# AudioThrowie.net
KiCad netlist of a schematic drawn in EAGLE
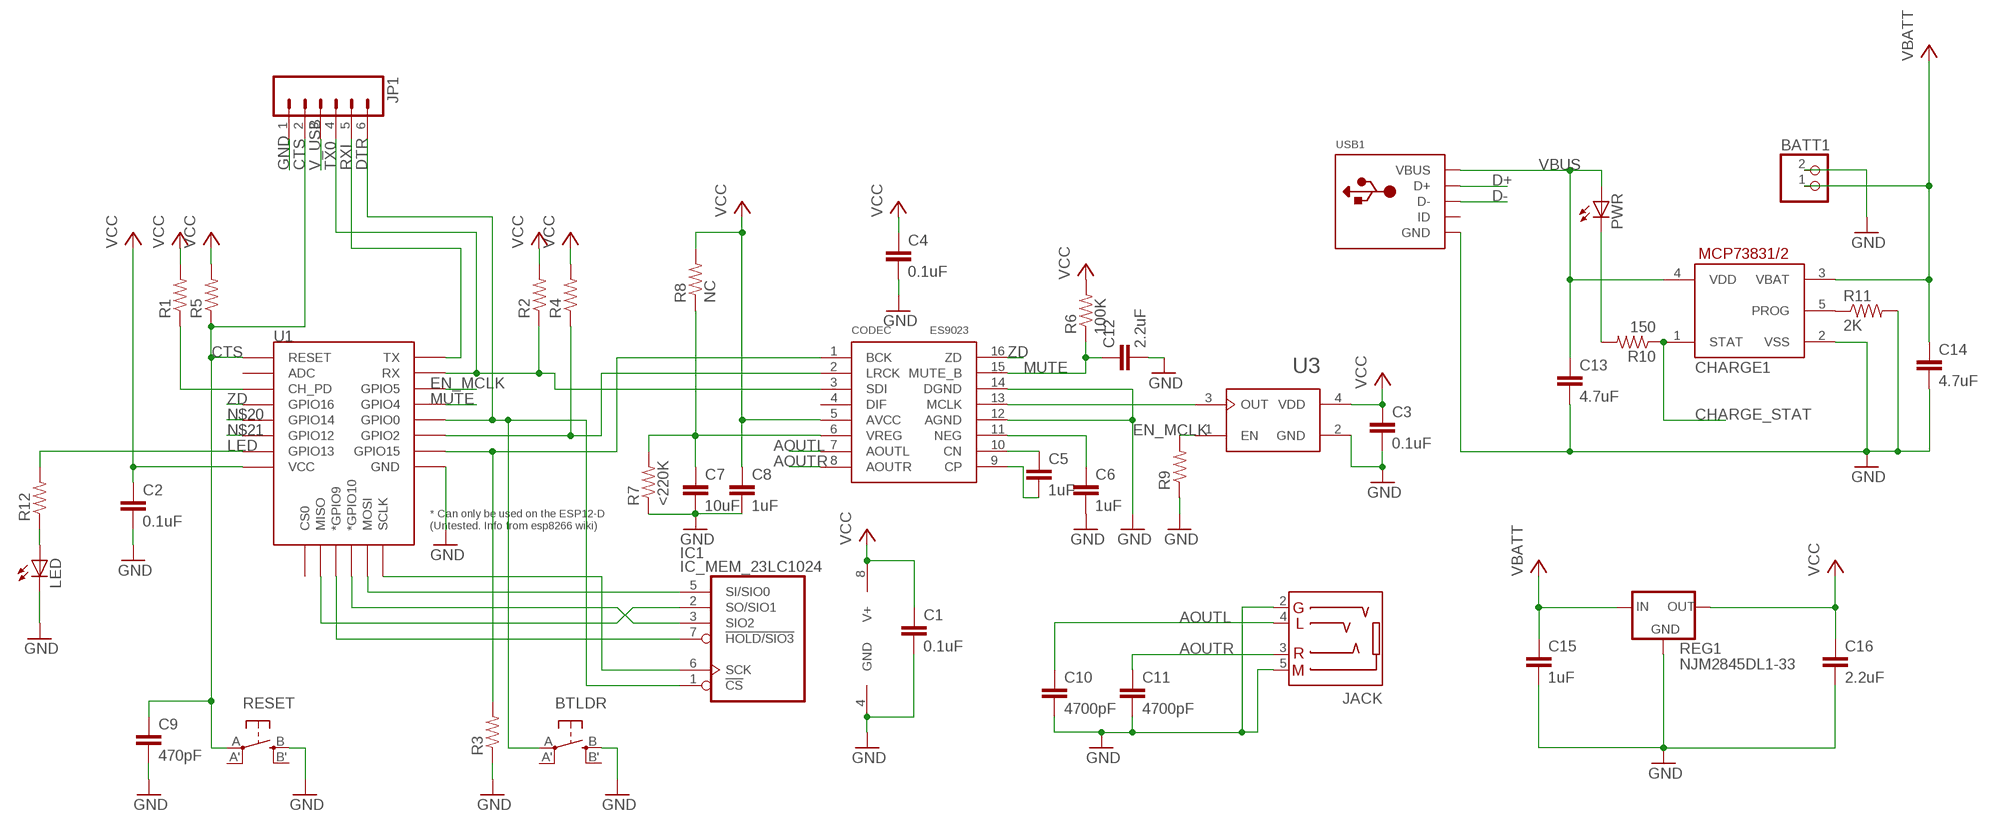
[diagram p0: schematic, sheet 1]

(export (version "E")
  (design (tool "Eeschema 10.0.6"))
  (components
    (comp (ref "BATT1")
      (value "JST_2PIN-THM")
      (footprint "eagle-import:JST-PH-2-THM")
      (libsource (lib "eagle-import") (part "JST_2PIN-THM"))
    )
    (comp (ref "BTLDR")
      (value "SPST_TACT-EVQQ2")
      (footprint "eagle-import:EVQ-Q2")
      (libsource (lib "eagle-import") (part "SPST_TACT-EVQQ2"))
    )
    (comp (ref "C1")
      (value "0.1uF")
      (footprint "eagle-import:0805")
      (libsource (lib "eagle-import") (part "CAP0805"))
    )
    (comp (ref "C2")
      (value "0.1uF")
      (footprint "eagle-import:0805")
      (libsource (lib "eagle-import") (part "CAP0805"))
    )
    (comp (ref "C3")
      (value "0.1uF")
      (footprint "eagle-import:0805")
      (libsource (lib "eagle-import") (part "CAP0805"))
    )
    (comp (ref "C4")
      (value "0.1uF")
      (footprint "eagle-import:0805")
      (libsource (lib "eagle-import") (part "CAP0805"))
    )
    (comp (ref "C5")
      (value "1uF")
      (footprint "eagle-import:0805")
      (libsource (lib "eagle-import") (part "CAP0805"))
    )
    (comp (ref "C6")
      (value "1uF")
      (footprint "eagle-import:0805")
      (libsource (lib "eagle-import") (part "CAP0805"))
    )
    (comp (ref "C7")
      (value "10uF")
      (footprint "eagle-import:0805")
      (libsource (lib "eagle-import") (part "CAP0805"))
    )
    (comp (ref "C8")
      (value "1uF")
      (footprint "eagle-import:0805")
      (libsource (lib "eagle-import") (part "CAP0805"))
    )
    (comp (ref "C9")
      (value "470pF")
      (footprint "eagle-import:0805")
      (libsource (lib "eagle-import") (part "CAP0805"))
    )
    (comp (ref "C10")
      (value "4700pF")
      (footprint "eagle-import:0805")
      (libsource (lib "eagle-import") (part "CAP0805"))
    )
    (comp (ref "C11")
      (value "4700pF")
      (footprint "eagle-import:0805")
      (libsource (lib "eagle-import") (part "CAP0805"))
    )
    (comp (ref "C12")
      (value "2.2uF")
      (footprint "eagle-import:0805")
      (libsource (lib "eagle-import") (part "CAP0805"))
    )
    (comp (ref "C13")
      (value "4.7uF")
      (footprint "eagle-import:0805")
      (libsource (lib "eagle-import") (part "CAP0805"))
    )
    (comp (ref "C14")
      (value "4.7uF")
      (footprint "eagle-import:0805")
      (libsource (lib "eagle-import") (part "CAP0805"))
    )
    (comp (ref "C15")
      (value "1uF")
      (footprint "eagle-import:0805")
      (libsource (lib "eagle-import") (part "CAP0805"))
    )
    (comp (ref "C16")
      (value "2.2uF")
      (footprint "eagle-import:0805")
      (libsource (lib "eagle-import") (part "CAP0805"))
    )
    (comp (ref "CHARGE1")
      (value "MCP73831/OT")
      (footprint "eagle-import:SOT23-5L")
      (libsource (lib "eagle-import") (part "MCP73831/OT"))
    )
    (comp (ref "CODEC")
      (value "ES9023")
      (footprint "eagle-import:SOP16")
      (libsource (lib "eagle-import") (part "ES9023"))
    )
    (comp (ref "IC1")
      (value "IC_MEM_23LC1024")
      (footprint "eagle-import:SOIC-8")
      (libsource (lib "eagle-import") (part "IC_MEM_23LC1024"))
    )
    (comp (ref "JACK")
      (value "AUDIO-STEREO-JACK-3.5MM-4SLEEVES")
      (footprint "eagle-import:PJ320D")
      (libsource (lib "eagle-import") (part "AUDIO-STEREO-JACK-3.5MM-4SLEEVES"))
    )
    (comp (ref "JP1")
      (value "M06LONGPADS")
      (footprint "eagle-import:1X06_LONGPADS")
      (libsource (lib "eagle-import") (part "M06LONGPADS"))
    )
    (comp (ref "LED")
      (value "LED3MM")
      (footprint "eagle-import:LED3MM")
      (libsource (lib "eagle-import") (part "LED3MM"))
    )
    (comp (ref "PWR")
      (value "LED3MM")
      (footprint "eagle-import:LED3MM")
      (libsource (lib "eagle-import") (part "LED3MM"))
    )
    (comp (ref "R1")
      (value "R-US_M0805")
      (footprint "eagle-import:M0805")
      (libsource (lib "eagle-import") (part "R-US_M0805"))
    )
    (comp (ref "R2")
      (value "R-US_M0805")
      (footprint "eagle-import:M0805")
      (libsource (lib "eagle-import") (part "R-US_M0805"))
    )
    (comp (ref "R3")
      (value "R-US_M0805")
      (footprint "eagle-import:M0805")
      (libsource (lib "eagle-import") (part "R-US_M0805"))
    )
    (comp (ref "R4")
      (value "R-US_M0805")
      (footprint "eagle-import:M0805")
      (libsource (lib "eagle-import") (part "R-US_M0805"))
    )
    (comp (ref "R5")
      (value "R-US_M0805")
      (footprint "eagle-import:M0805")
      (libsource (lib "eagle-import") (part "R-US_M0805"))
    )
    (comp (ref "R6")
      (value "100K")
      (footprint "eagle-import:M0805")
      (libsource (lib "eagle-import") (part "R-US_M0805"))
    )
    (comp (ref "R7")
      (value "<220K")
      (footprint "eagle-import:M0805")
      (libsource (lib "eagle-import") (part "R-US_M0805"))
    )
    (comp (ref "R8")
      (value "NC")
      (footprint "eagle-import:M0805")
      (libsource (lib "eagle-import") (part "R-US_M0805"))
    )
    (comp (ref "R9")
      (value "R-US_M0805")
      (footprint "eagle-import:M0805")
      (libsource (lib "eagle-import") (part "R-US_M0805"))
    )
    (comp (ref "R10")
      (value "150")
      (footprint "eagle-import:R0805")
      (libsource (lib "eagle-import") (part "R-US_R0805"))
    )
    (comp (ref "R11")
      (value "2K")
      (footprint "eagle-import:R0603")
      (libsource (lib "eagle-import") (part "R-US_R0603"))
    )
    (comp (ref "R12")
      (value "R-US_M0805")
      (footprint "eagle-import:M0805")
      (libsource (lib "eagle-import") (part "R-US_M0805"))
    )
    (comp (ref "REG1")
      (value "NJM2845DL1-33")
      (footprint "eagle-import:DPACK")
      (libsource (lib "eagle-import") (part "LP2950?CDT-3.3"))
    )
    (comp (ref "RESET")
      (value "SPST_TACT-EVQQ2")
      (footprint "eagle-import:EVQ-Q2")
      (libsource (lib "eagle-import") (part "SPST_TACT-EVQQ2"))
    )
    (comp (ref "U1")
      (value "ESP12ESMD")
      (footprint "eagle-import:ESP12E-SMD")
      (libsource (lib "eagle-import") (part "ESP12ESMD"))
    )
    (comp (ref "U3")
      (value "OSCILLATOR-AW-2.5X2")
      (footprint "eagle-import:AW-CRYSTAL-2.5X2")
      (libsource (lib "eagle-import") (part "OSCILLATOR-AW-2.5X2"))
    )
    (comp (ref "USB1")
      (value "USBMINIB")
      (footprint "eagle-import:USB-MINIB")
      (libsource (lib "eagle-import") (part "USBMINIB"))
    )
  )
  (nets
    (net (code "1") (name "/AOUTL") (class "Default")
      (node (ref "C10") (pin "1") (pinfunction "1_1") (pintype "passive"))
      (node (ref "CODEC") (pin "7") (pinfunction "AOUTL_7") (pintype "bidirectional"))
      (node (ref "JACK") (pin "4") (pinfunction "TIP_4") (pintype "bidirectional"))
    )
    (net (code "2") (name "/AOUTR") (class "Default")
      (node (ref "C11") (pin "1") (pinfunction "1_1") (pintype "passive"))
      (node (ref "CODEC") (pin "8") (pinfunction "AOUTR_8") (pintype "bidirectional"))
      (node (ref "JACK") (pin "3") (pinfunction "RING1_3") (pintype "bidirectional"))
    )
    (net (code "3") (name "/CHARGE_STAT") (class "Default")
      (node (ref "CHARGE1") (pin "1") (pinfunction "STAT_1") (pintype "output"))
      (node (ref "R10") (pin "1") (pinfunction "1_1") (pintype "passive"))
    )
    (net (code "4") (name "/CTS") (class "Default")
      (node (ref "C9") (pin "1") (pinfunction "1_1") (pintype "passive"))
      (node (ref "JP1") (pin "2") (pinfunction "2_2") (pintype "passive"))
      (node (ref "R5") (pin "1") (pinfunction "1_1") (pintype "passive"))
      (node (ref "RESET") (pin "A") (pinfunction "P_A") (pintype "passive"))
      (node (ref "U1") (pin "RESET") (pinfunction "RESET_RESET") (pintype "bidirectional"))
    )
    (net (code "5") (name "/D+") (class "Default")
      (node (ref "USB1") (pin "D+") (pinfunction "D+_D+") (pintype "bidirectional"))
    )
    (net (code "6") (name "/D-") (class "Default")
      (node (ref "USB1") (pin "D-") (pinfunction "D-_D-") (pintype "bidirectional"))
    )
    (net (code "7") (name "/DTR") (class "Default")
      (node (ref "BTLDR") (pin "A") (pinfunction "P_A") (pintype "passive"))
      (node (ref "IC1") (pin "1") (pinfunction "~{CS}_1") (pintype "input"))
      (node (ref "JP1") (pin "6") (pinfunction "6_6") (pintype "passive"))
      (node (ref "U1") (pin "GPIO0") (pinfunction "GPIO0_GPIO0") (pintype "bidirectional"))
    )
    (net (code "8") (name "/EN_MCLK") (class "Default")
      (node (ref "R9") (pin "2") (pinfunction "2_2") (pintype "passive"))
      (node (ref "U1") (pin "GPIO5") (pinfunction "GPIO5_GPIO5") (pintype "bidirectional"))
      (node (ref "U3") (pin "1") (pinfunction "EN_1") (pintype "input"))
    )
    (net (code "9") (name "/LED") (class "Default")
      (node (ref "R12") (pin "2") (pinfunction "2_2") (pintype "passive"))
      (node (ref "U1") (pin "GPIO13") (pinfunction "GPIO13_GPIO13") (pintype "bidirectional"))
    )
    (net (code "10") (name "/MUTE") (class "Default")
      (node (ref "C12") (pin "1") (pinfunction "1_1") (pintype "passive"))
      (node (ref "CODEC") (pin "15") (pinfunction "MUTE_B_15") (pintype "bidirectional"))
      (node (ref "R6") (pin "1") (pinfunction "1_1") (pintype "passive"))
      (node (ref "U1") (pin "GPIO4") (pinfunction "GPIO4_GPIO4") (pintype "bidirectional"))
    )
    (net (code "11") (name "/N$20") (class "Default")
      (node (ref "U1") (pin "GPIO14") (pinfunction "GPIO14_GPIO14") (pintype "bidirectional"))
    )
    (net (code "12") (name "/N$21") (class "Default")
      (node (ref "U1") (pin "GPIO12") (pinfunction "GPIO12_GPIO12") (pintype "bidirectional"))
    )
    (net (code "13") (name "/RXI") (class "Default")
      (node (ref "JP1") (pin "5") (pinfunction "5_5") (pintype "passive"))
      (node (ref "U1") (pin "TXD0") (pinfunction "TX_TXD0") (pintype "bidirectional"))
    )
    (net (code "14") (name "/TX0") (class "Default")
      (node (ref "CODEC") (pin "3") (pinfunction "SDI_3") (pintype "bidirectional"))
      (node (ref "JP1") (pin "4") (pinfunction "4_4") (pintype "passive"))
      (node (ref "R2") (pin "1") (pinfunction "1_1") (pintype "passive"))
      (node (ref "U1") (pin "RXD0") (pinfunction "RX_RXD0") (pintype "bidirectional"))
    )
    (net (code "15") (name "/VBUS") (class "Default")
      (node (ref "C13") (pin "1") (pinfunction "1_1") (pintype "passive"))
      (node (ref "CHARGE1") (pin "4") (pinfunction "VDD_4") (pintype "power_in"))
      (node (ref "PWR") (pin "A") (pinfunction "A_A") (pintype "passive"))
      (node (ref "USB1") (pin "VBUS") (pinfunction "VBUS_VBUS") (pintype "power_in"))
    )
    (net (code "16") (name "/V_USB") (class "Default")
      (node (ref "JP1") (pin "3") (pinfunction "3_3") (pintype "passive"))
    )
    (net (code "17") (name "/ZD") (class "Default")
      (node (ref "CODEC") (pin "16") (pinfunction "ZD_16") (pintype "bidirectional"))
      (node (ref "U1") (pin "GPIO16") (pinfunction "GPIO16_GPIO16") (pintype "bidirectional"))
    )
    (net (code "18") (name "GND") (class "Default")
      (node (ref "BATT1") (pin "2") (pinfunction "1_2") (pintype "passive"))
      (node (ref "BTLDR") (pin "B") (pinfunction "S_B") (pintype "passive"))
      (node (ref "C1") (pin "2") (pinfunction "2_2") (pintype "passive"))
      (node (ref "C10") (pin "2") (pinfunction "2_2") (pintype "passive"))
      (node (ref "C11") (pin "2") (pinfunction "2_2") (pintype "passive"))
      (node (ref "C12") (pin "2") (pinfunction "2_2") (pintype "passive"))
      (node (ref "C13") (pin "2") (pinfunction "2_2") (pintype "passive"))
      (node (ref "C14") (pin "2") (pinfunction "2_2") (pintype "passive"))
      (node (ref "C15") (pin "2") (pinfunction "2_2") (pintype "passive"))
      (node (ref "C16") (pin "2") (pinfunction "2_2") (pintype "passive"))
      (node (ref "C2") (pin "2") (pinfunction "2_2") (pintype "passive"))
      (node (ref "C3") (pin "2") (pinfunction "2_2") (pintype "passive"))
      (node (ref "C4") (pin "2") (pinfunction "2_2") (pintype "passive"))
      (node (ref "C6") (pin "2") (pinfunction "2_2") (pintype "passive"))
      (node (ref "C7") (pin "2") (pinfunction "2_2") (pintype "passive"))
      (node (ref "C8") (pin "2") (pinfunction "2_2") (pintype "passive"))
      (node (ref "C9") (pin "2") (pinfunction "2_2") (pintype "passive"))
      (node (ref "CHARGE1") (pin "2") (pinfunction "VSS_2") (pintype "power_in"))
      (node (ref "CODEC") (pin "12") (pinfunction "AGND_12") (pintype "bidirectional"))
      (node (ref "CODEC") (pin "14") (pinfunction "DGND_14") (pintype "bidirectional"))
      (node (ref "IC1") (pin "4") (pinfunction "GND_4") (pintype "power_in"))
      (node (ref "JACK") (pin "2") (pinfunction "RING2_2") (pintype "bidirectional"))
      (node (ref "JACK") (pin "5") (pinfunction "SLEEVE_5") (pintype "bidirectional"))
      (node (ref "JP1") (pin "1") (pinfunction "1_1") (pintype "passive"))
      (node (ref "LED") (pin "K") (pinfunction "C_K") (pintype "passive"))
      (node (ref "R11") (pin "2") (pinfunction "2_2") (pintype "passive"))
      (node (ref "R3") (pin "1") (pinfunction "1_1") (pintype "passive"))
      (node (ref "R7") (pin "1") (pinfunction "1_1") (pintype "passive"))
      (node (ref "R9") (pin "1") (pinfunction "1_1") (pintype "passive"))
      (node (ref "REG1") (pin "4") (pinfunction "GND_4") (pintype "input"))
      (node (ref "RESET") (pin "B") (pinfunction "S_B") (pintype "passive"))
      (node (ref "U1") (pin "GND") (pinfunction "GND_GND") (pintype "bidirectional"))
      (node (ref "U3") (pin "2") (pinfunction "GND_2") (pintype "power_in"))
      (node (ref "USB1") (pin "GND") (pinfunction "GND_GND") (pintype "power_in"))
    )
    (net (code "19") (name "Net-(CHARGE1-PROG)") (class "Default")
      (node (ref "CHARGE1") (pin "5") (pinfunction "PROG_5") (pintype "input"))
      (node (ref "R11") (pin "1") (pinfunction "1_1") (pintype "passive"))
    )
    (net (code "20") (name "Net-(CODEC-BCK)") (class "Default")
      (node (ref "CODEC") (pin "1") (pinfunction "BCK_1") (pintype "bidirectional"))
      (node (ref "R3") (pin "2") (pinfunction "2_2") (pintype "passive"))
      (node (ref "U1") (pin "GPIO15") (pinfunction "GPIO15_GPIO15") (pintype "bidirectional"))
    )
    (net (code "21") (name "Net-(CODEC-CN)") (class "Default")
      (node (ref "C5") (pin "1") (pinfunction "1_1") (pintype "passive"))
      (node (ref "CODEC") (pin "10") (pinfunction "CN_10") (pintype "bidirectional"))
    )
    (net (code "22") (name "Net-(CODEC-CP)") (class "Default")
      (node (ref "C5") (pin "2") (pinfunction "2_2") (pintype "passive"))
      (node (ref "CODEC") (pin "9") (pinfunction "CP_9") (pintype "bidirectional"))
    )
    (net (code "23") (name "Net-(CODEC-LRCK)") (class "Default")
      (node (ref "CODEC") (pin "2") (pinfunction "LRCK_2") (pintype "bidirectional"))
      (node (ref "R4") (pin "1") (pinfunction "1_1") (pintype "passive"))
      (node (ref "U1") (pin "GPIO2") (pinfunction "GPIO2_GPIO2") (pintype "bidirectional"))
    )
    (net (code "24") (name "Net-(CODEC-MCLK)") (class "Default")
      (node (ref "CODEC") (pin "13") (pinfunction "MCLK_13") (pintype "bidirectional"))
      (node (ref "U3") (pin "3") (pinfunction "OUT_3") (pintype "bidirectional"))
    )
    (net (code "25") (name "Net-(CODEC-NEG)") (class "Default")
      (node (ref "C6") (pin "1") (pinfunction "1_1") (pintype "passive"))
      (node (ref "CODEC") (pin "11") (pinfunction "NEG_11") (pintype "bidirectional"))
    )
    (net (code "26") (name "Net-(CODEC-VREG)") (class "Default")
      (node (ref "C7") (pin "1") (pinfunction "1_1") (pintype "passive"))
      (node (ref "CODEC") (pin "6") (pinfunction "VREG_6") (pintype "bidirectional"))
      (node (ref "R7") (pin "2") (pinfunction "2_2") (pintype "passive"))
      (node (ref "R8") (pin "1") (pinfunction "1_1") (pintype "passive"))
    )
    (net (code "27") (name "Net-(IC1A-SCK)") (class "Default")
      (node (ref "IC1") (pin "6") (pinfunction "SCK_6") (pintype "input"))
      (node (ref "U1") (pin "SCLK") (pinfunction "SCLK_SCLK") (pintype "bidirectional"))
    )
    (net (code "28") (name "Net-(IC1A-SIO2)") (class "Default")
      (node (ref "IC1") (pin "3") (pinfunction "SIO2_3") (pintype "bidirectional"))
      (node (ref "U1") (pin "GPIO10") (pinfunction "*GPIO10_GPIO10") (pintype "bidirectional"))
    )
    (net (code "29") (name "Net-(IC1A-SI{slash}SIO0)") (class "Default")
      (node (ref "IC1") (pin "5") (pinfunction "SI/SIO0_5") (pintype "bidirectional"))
      (node (ref "U1") (pin "MOSI") (pinfunction "MOSI_MOSI") (pintype "bidirectional"))
    )
    (net (code "30") (name "Net-(IC1A-SO{slash}SIO1)") (class "Default")
      (node (ref "IC1") (pin "2") (pinfunction "SO/SIO1_2") (pintype "bidirectional"))
      (node (ref "U1") (pin "MISO") (pinfunction "MISO_MISO") (pintype "bidirectional"))
    )
    (net (code "31") (name "Net-(IC1A-~{HOLD{slash}SIO3})") (class "Default")
      (node (ref "IC1") (pin "7") (pinfunction "~{HOLD/SIO3}_7") (pintype "input"))
      (node (ref "U1") (pin "GPIO9") (pinfunction "*GPIO9_GPIO9") (pintype "bidirectional"))
    )
    (net (code "32") (name "Net-(LED-PadA)") (class "Default")
      (node (ref "LED") (pin "A") (pinfunction "A_A") (pintype "passive"))
      (node (ref "R12") (pin "1") (pinfunction "1_1") (pintype "passive"))
    )
    (net (code "33") (name "Net-(PWR-C)") (class "Default")
      (node (ref "PWR") (pin "K") (pinfunction "C_K") (pintype "passive"))
      (node (ref "R10") (pin "2") (pinfunction "2_2") (pintype "passive"))
    )
    (net (code "34") (name "Net-(R1-Pad1)") (class "Default")
      (node (ref "R1") (pin "1") (pinfunction "1_1") (pintype "passive"))
      (node (ref "U1") (pin "CH_PD") (pinfunction "CH_PD_CH_PD") (pintype "bidirectional"))
    )
    (net (code "35") (name "VBATT") (class "Default")
      (node (ref "BATT1") (pin "1") (pinfunction "2_1") (pintype "passive"))
      (node (ref "C14") (pin "1") (pinfunction "1_1") (pintype "passive"))
      (node (ref "C15") (pin "1") (pinfunction "1_1") (pintype "passive"))
      (node (ref "CHARGE1") (pin "3") (pinfunction "VBAT_3") (pintype "bidirectional"))
      (node (ref "REG1") (pin "1") (pinfunction "IN_1") (pintype "input"))
    )
    (net (code "36") (name "VCC") (class "Default")
      (node (ref "C1") (pin "1") (pinfunction "1_1") (pintype "passive"))
      (node (ref "C16") (pin "1") (pinfunction "1_1") (pintype "passive"))
      (node (ref "C2") (pin "1") (pinfunction "1_1") (pintype "passive"))
      (node (ref "C3") (pin "1") (pinfunction "1_1") (pintype "passive"))
      (node (ref "C4") (pin "1") (pinfunction "1_1") (pintype "passive"))
      (node (ref "C8") (pin "1") (pinfunction "1_1") (pintype "passive"))
      (node (ref "CODEC") (pin "5") (pinfunction "AVCC_5") (pintype "bidirectional"))
      (node (ref "IC1") (pin "8") (pinfunction "V+_8") (pintype "power_in"))
      (node (ref "R1") (pin "2") (pinfunction "2_2") (pintype "passive"))
      (node (ref "R2") (pin "2") (pinfunction "2_2") (pintype "passive"))
      (node (ref "R4") (pin "2") (pinfunction "2_2") (pintype "passive"))
      (node (ref "R5") (pin "2") (pinfunction "2_2") (pintype "passive"))
      (node (ref "R6") (pin "2") (pinfunction "2_2") (pintype "passive"))
      (node (ref "R8") (pin "2") (pinfunction "2_2") (pintype "passive"))
      (node (ref "REG1") (pin "3") (pinfunction "OUT_3") (pintype "passive"))
      (node (ref "U1") (pin "VCC") (pinfunction "VCC_VCC") (pintype "bidirectional"))
      (node (ref "U3") (pin "4") (pinfunction "VDD_4") (pintype "power_in"))
    )
    (net (code "37") (name "unconnected-(BTLDR-P1-PadA')") (class "Default")
      (node (ref "BTLDR") (pin "A'") (pinfunction "P1_A'") (pintype "passive"))
    )
    (net (code "38") (name "unconnected-(BTLDR-S1-PadB')") (class "Default")
      (node (ref "BTLDR") (pin "B'") (pinfunction "S1_B'") (pintype "passive"))
    )
    (net (code "39") (name "unconnected-(CODEC-DIF-Pad4)") (class "Default")
      (node (ref "CODEC") (pin "4") (pinfunction "DIF_4") (pintype "bidirectional"))
    )
    (net (code "40") (name "unconnected-(RESET-P1-PadA')") (class "Default")
      (node (ref "RESET") (pin "A'") (pinfunction "P1_A'") (pintype "passive"))
    )
    (net (code "41") (name "unconnected-(RESET-S1-PadB')") (class "Default")
      (node (ref "RESET") (pin "B'") (pinfunction "S1_B'") (pintype "passive"))
    )
    (net (code "42") (name "unconnected-(U1-PadADC)") (class "Default")
      (node (ref "U1") (pin "ADC") (pinfunction "ADC_ADC") (pintype "bidirectional"))
    )
    (net (code "43") (name "unconnected-(U1-PadCS0)") (class "Default")
      (node (ref "U1") (pin "CS0") (pinfunction "CS0_CS0") (pintype "bidirectional"))
    )
    (net (code "44") (name "unconnected-(USB1-PadID)") (class "Default")
      (node (ref "USB1") (pin "ID") (pinfunction "ID_ID") (pintype "bidirectional"))
    )
  )
)
